# Cellphone-Detector-LM358-Flip-Flop-2X.net
KiCad netlist of a schematic drawn in EAGLE
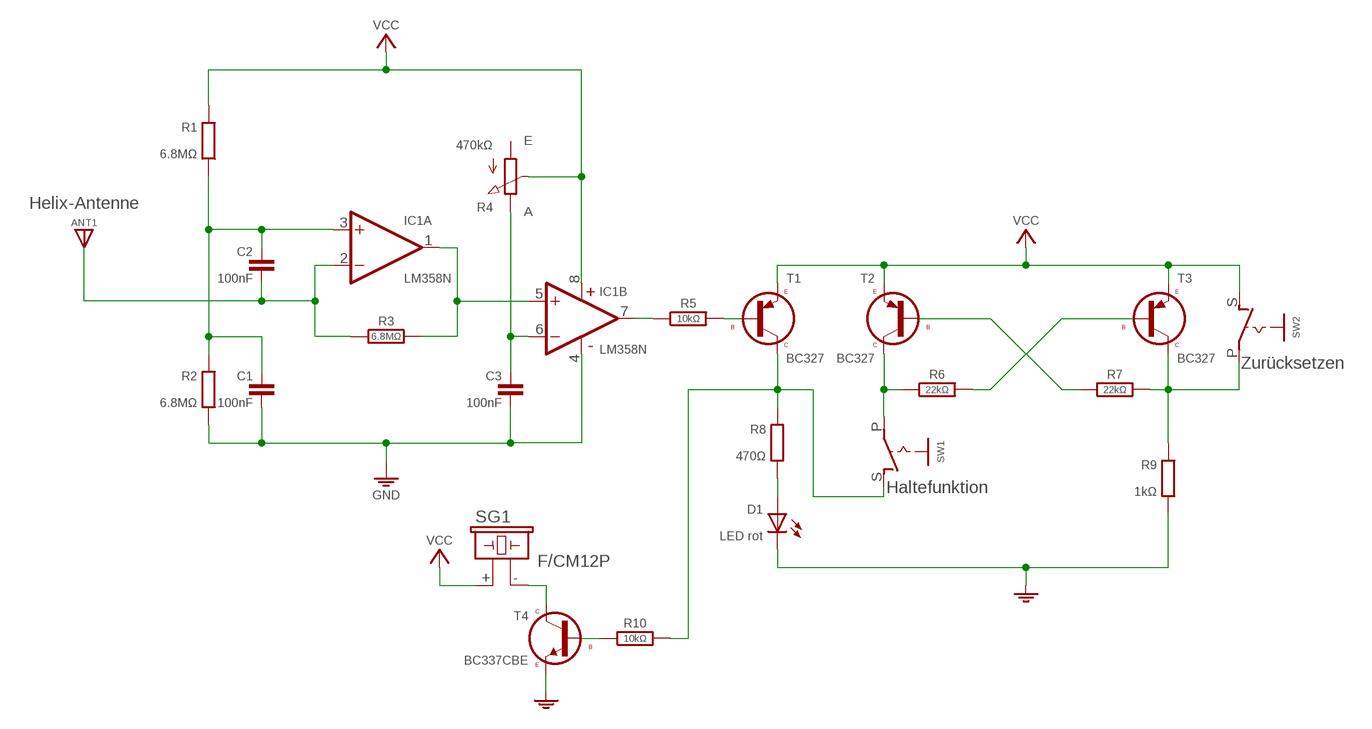
[diagram p0: schematic, sheet 1]

(export (version "E")
  (design (tool "Eeschema 10.0.6"))
  (components
    (comp (ref "ANT1")
      (value "ANT")
      (footprint "eagle-import:SPAD")
      (libsource (lib "eagle-import") (part "ANT"))
    )
    (comp (ref "C1")
      (value "100nF")
      (footprint "eagle-import:C050-025X060")
      (libsource (lib "eagle-import") (part "C025-025X060"))
    )
    (comp (ref "C2")
      (value "100nF")
      (footprint "eagle-import:C025-024X044")
      (libsource (lib "eagle-import") (part "C025-024X044"))
    )
    (comp (ref "C3")
      (value "100nF")
      (footprint "eagle-import:C025-024X044")
      (libsource (lib "eagle-import") (part "C025-024X044"))
    )
    (comp (ref "D1")
      (value "LED rot")
      (footprint "eagle-import:LED_3MM_V")
      (libsource (lib "eagle-import") (part "LED-3MM/V"))
    )
    (comp (ref "IC1")
      (value "LM358N")
      (footprint "eagle-import:DIL08")
      (libsource (lib "eagle-import") (part "LM358N"))
    )
    (comp (ref "R1")
      (value "6.8MΩ")
      (footprint "eagle-import:0204_2")
      (libsource (lib "eagle-import") (part "R0204/2"))
    )
    (comp (ref "R2")
      (value "6.8MΩ")
      (footprint "eagle-import:0204_2V")
      (libsource (lib "eagle-import") (part "R0204/2V"))
    )
    (comp (ref "R3")
      (value "6.8MΩ")
      (footprint "eagle-import:0202_2V")
      (libsource (lib "eagle-import") (part "R-H0202/2V"))
    )
    (comp (ref "R4")
      (value "470kΩ")
      (footprint "eagle-import:CONN-3P")
      (libsource (lib "eagle-import") (part "POT-3P"))
    )
    (comp (ref "R5")
      (value "10kΩ")
      (footprint "eagle-import:0204_10")
      (libsource (lib "eagle-import") (part "R-H0204/10"))
    )
    (comp (ref "R6")
      (value "22kΩ")
      (footprint "eagle-import:0204_10")
      (libsource (lib "eagle-import") (part "R-H0204/10"))
    )
    (comp (ref "R7")
      (value "22kΩ")
      (footprint "eagle-import:0204_10")
      (libsource (lib "eagle-import") (part "R-H0204/10"))
    )
    (comp (ref "R8")
      (value "470Ω")
      (footprint "eagle-import:0204_10-V")
      (libsource (lib "eagle-import") (part "R0204/10-V"))
    )
    (comp (ref "R9")
      (value "1kΩ")
      (footprint "eagle-import:0204_10")
      (libsource (lib "eagle-import") (part "R0204/10"))
    )
    (comp (ref "R10")
      (value "10kΩ")
      (footprint "eagle-import:0204_10")
      (libsource (lib "eagle-import") (part "R-H0204/10"))
    )
    (comp (ref "S1")
      (value "VCC_GNDR")
      (footprint "eagle-import:SPAD+-")
      (libsource (lib "eagle-import") (part "VCC_GNDR"))
    )
    (comp (ref "SG1")
      (value "F/CM12P")
      (footprint "eagle-import:F_CM12P")
      (libsource (lib "eagle-import") (part "F/CM12P"))
    )
    (comp (ref "SW1")
      (value "SW1")
      (footprint "eagle-import:SLSW-1P1T")
      (libsource (lib "eagle-import") (part "SL-SW-1P-1T"))
    )
    (comp (ref "SW2")
      (value "PB-1P-1T-2P")
      (footprint "eagle-import:SLSW-1P1T")
      (libsource (lib "eagle-import") (part "PB-1P-1T-2P"))
    )
    (comp (ref "T1")
      (value "BC327")
      (footprint "eagle-import:TO92")
      (libsource (lib "eagle-import") (part "BC327"))
    )
    (comp (ref "T2")
      (value "BC327")
      (footprint "eagle-import:TO92")
      (libsource (lib "eagle-import") (part "BC327"))
    )
    (comp (ref "T3")
      (value "BC327")
      (footprint "eagle-import:TO92")
      (libsource (lib "eagle-import") (part "BC327"))
    )
    (comp (ref "T4")
      (value "BC337CBE")
      (footprint "eagle-import:TO92-CBE")
      (libsource (lib "eagle-import") (part "BC337CBE"))
    )
  )
  (nets
    (net (code "1") (name "GND") (class "Default")
      (node (ref "C1") (pin "2") (pinfunction "2_2") (pintype "passive"))
      (node (ref "C3") (pin "2") (pinfunction "2_2") (pintype "passive"))
      (node (ref "D1") (pin "K") (pinfunction "C_K") (pintype "passive"))
      (node (ref "IC1") (pin "4") (pinfunction "V-_4") (pintype "power_in"))
      (node (ref "R2") (pin "2") (pinfunction "1_2") (pintype "passive"))
      (node (ref "R9") (pin "2") (pinfunction "1_2") (pintype "passive"))
      (node (ref "S1") (pin "1") (pinfunction "GND_1") (pintype "power_in"))
      (node (ref "T4") (pin "3") (pinfunction "E_3") (pintype "passive"))
    )
    (net (code "2") (name "Net-(IC1A-+IN)") (class "Default")
      (node (ref "C1") (pin "1") (pinfunction "1_1") (pintype "passive"))
      (node (ref "C2") (pin "1") (pinfunction "1_1") (pintype "passive"))
      (node (ref "IC1") (pin "3") (pinfunction "+IN_3") (pintype "input"))
      (node (ref "R1") (pin "2") (pinfunction "1_2") (pintype "passive"))
      (node (ref "R2") (pin "1") (pinfunction "2_1") (pintype "passive"))
    )
    (net (code "3") (name "Net-(IC1A--IN)") (class "Default")
      (node (ref "ANT1") (pin "1") (pinfunction "1_1") (pintype "output"))
      (node (ref "C2") (pin "2") (pinfunction "2_2") (pintype "passive"))
      (node (ref "IC1") (pin "2") (pinfunction "-IN_2") (pintype "input"))
      (node (ref "R3") (pin "1") (pinfunction "1_1") (pintype "passive"))
    )
    (net (code "4") (name "Net-(IC1A-OUT)") (class "Default")
      (node (ref "IC1") (pin "1") (pinfunction "OUT_1") (pintype "output"))
      (node (ref "IC1") (pin "5") (pinfunction "+IN_5") (pintype "input"))
      (node (ref "R3") (pin "2") (pinfunction "2_2") (pintype "passive"))
    )
    (net (code "5") (name "Net-(IC1B--IN)") (class "Default")
      (node (ref "C3") (pin "1") (pinfunction "1_1") (pintype "passive"))
      (node (ref "IC1") (pin "6") (pinfunction "-IN_6") (pintype "input"))
      (node (ref "R4") (pin "3") (pinfunction "E_3") (pintype "passive"))
    )
    (net (code "6") (name "Net-(IC1B-OUT)") (class "Default")
      (node (ref "IC1") (pin "7") (pinfunction "OUT_7") (pintype "output"))
      (node (ref "R5") (pin "1") (pinfunction "1_1") (pintype "passive"))
    )
    (net (code "7") (name "Net-(R8-1)") (class "Default")
      (node (ref "D1") (pin "A") (pinfunction "A_A") (pintype "passive"))
      (node (ref "R8") (pin "2") (pinfunction "1_2") (pintype "passive"))
    )
    (net (code "8") (name "Net-(R8-2)") (class "Default")
      (node (ref "R10") (pin "2") (pinfunction "2_2") (pintype "passive"))
      (node (ref "R8") (pin "1") (pinfunction "2_1") (pintype "passive"))
      (node (ref "SW1") (pin "S") (pinfunction "S_S") (pintype "passive"))
      (node (ref "T1") (pin "1") (pinfunction "C_1") (pintype "passive"))
    )
    (net (code "9") (name "Net-(R9-2)") (class "Default")
      (node (ref "R7") (pin "2") (pinfunction "2_2") (pintype "passive"))
      (node (ref "R9") (pin "1") (pinfunction "2_1") (pintype "passive"))
      (node (ref "SW2") (pin "P") (pinfunction "P_P") (pintype "passive"))
      (node (ref "T3") (pin "1") (pinfunction "C_1") (pintype "passive"))
    )
    (net (code "10") (name "Net-(SG1-2)") (class "Default")
      (node (ref "SG1") (pin "-") (pinfunction "2_-") (pintype "passive"))
      (node (ref "T4") (pin "1") (pinfunction "C_1") (pintype "passive"))
    )
    (net (code "11") (name "Net-(T1-B)") (class "Default")
      (node (ref "R5") (pin "2") (pinfunction "2_2") (pintype "passive"))
      (node (ref "T1") (pin "2") (pinfunction "B_2") (pintype "passive"))
    )
    (net (code "12") (name "Net-(T2-B)") (class "Default")
      (node (ref "R7") (pin "1") (pinfunction "1_1") (pintype "passive"))
      (node (ref "T2") (pin "2") (pinfunction "B_2") (pintype "passive"))
    )
    (net (code "13") (name "Net-(T2-C)") (class "Default")
      (node (ref "R6") (pin "1") (pinfunction "1_1") (pintype "passive"))
      (node (ref "SW1") (pin "P") (pinfunction "P_P") (pintype "passive"))
      (node (ref "T2") (pin "1") (pinfunction "C_1") (pintype "passive"))
    )
    (net (code "14") (name "Net-(T3-B)") (class "Default")
      (node (ref "R6") (pin "2") (pinfunction "2_2") (pintype "passive"))
      (node (ref "T3") (pin "2") (pinfunction "B_2") (pintype "passive"))
    )
    (net (code "15") (name "Net-(T4-B)") (class "Default")
      (node (ref "R10") (pin "1") (pinfunction "1_1") (pintype "passive"))
      (node (ref "T4") (pin "2") (pinfunction "B_2") (pintype "passive"))
    )
    (net (code "16") (name "VCC") (class "Default")
      (node (ref "IC1") (pin "8") (pinfunction "V+_8") (pintype "power_in"))
      (node (ref "R1") (pin "1") (pinfunction "2_1") (pintype "passive"))
      (node (ref "R4") (pin "2") (pinfunction "S_2") (pintype "passive"))
      (node (ref "S1") (pin "2") (pinfunction "VCC_2") (pintype "power_in"))
      (node (ref "SG1") (pin "+") (pinfunction "1_+") (pintype "passive"))
      (node (ref "SW2") (pin "S") (pinfunction "S_S") (pintype "passive"))
      (node (ref "T1") (pin "3") (pinfunction "E_3") (pintype "passive"))
      (node (ref "T2") (pin "3") (pinfunction "E_3") (pintype "passive"))
      (node (ref "T3") (pin "3") (pinfunction "E_3") (pintype "passive"))
    )
    (net (code "17") (name "unconnected-(R4-A-Pad1)") (class "Default")
      (node (ref "R4") (pin "1") (pinfunction "A_1") (pintype "passive"))
    )
  )
)
